# signal_conditioner.net
KiCad netlist of a schematic drawn in EAGLE
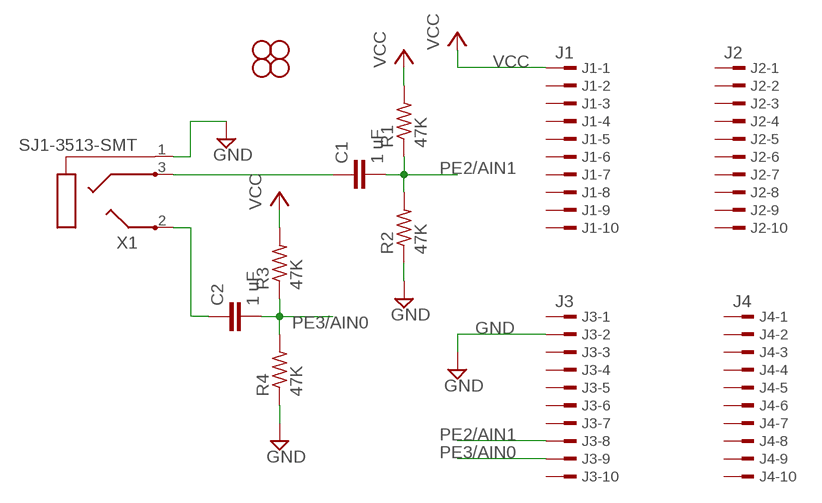
[diagram p0: schematic, sheet 1]

(export (version "E")
  (design (tool "Eeschema 10.0.6"))
  (components
    (comp (ref "C1")
      (value "1 uF")
      (footprint "eagle-import:C050-025X075")
      (libsource (lib "eagle-import") (part "C-EU050-025X075"))
    )
    (comp (ref "C2")
      (value "1 uF")
      (footprint "eagle-import:C050-025X075")
      (libsource (lib "eagle-import") (part "C-EU050-025X075"))
    )
    (comp (ref "J1")
      (value "J1")
      (footprint "eagle-import:TSW-110-02-S-S")
      (fields (field (name "OC_FARNELL") "unknown") (field (name "OC_NEWARK") "unknown"))
      (libsource (lib "eagle-import") (part "TSW-110-02-S-S"))
    )
    (comp (ref "J2")
      (value "J2")
      (footprint "eagle-import:TSW-110-02-S-S")
      (libsource (lib "eagle-import") (part "TSW-110-02-S-S"))
    )
    (comp (ref "J3")
      (value "J3")
      (footprint "eagle-import:TSW-110-02-S-S")
      (fields (field (name "OC_FARNELL") "unknown") (field (name "OC_NEWARK") "unknown"))
      (libsource (lib "eagle-import") (part "TSW-110-02-S-S"))
    )
    (comp (ref "J4")
      (value "J4")
      (footprint "eagle-import:TSW-110-02-S-S")
      (fields (field (name "OC_FARNELL") "unknown") (field (name "OC_NEWARK") "unknown"))
      (libsource (lib "eagle-import") (part "TSW-110-02-S-S"))
    )
    (comp (ref "JP1")
      (value "STAND-OFF")
      (footprint "eagle-import:STAND-OFF")
      (libsource (lib "eagle-import") (part "STAND-OFF"))
    )
    (comp (ref "JP2")
      (value "STAND-OFF")
      (footprint "eagle-import:STAND-OFF")
      (libsource (lib "eagle-import") (part "STAND-OFF"))
    )
    (comp (ref "JP3")
      (value "STAND-OFF")
      (footprint "eagle-import:STAND-OFF")
      (libsource (lib "eagle-import") (part "STAND-OFF"))
    )
    (comp (ref "JP4")
      (value "STAND-OFF")
      (footprint "eagle-import:STAND-OFF")
      (libsource (lib "eagle-import") (part "STAND-OFF"))
    )
    (comp (ref "R1")
      (value "47K")
      (footprint "eagle-import:0207_7")
      (libsource (lib "eagle-import") (part "R-US_0207/7"))
    )
    (comp (ref "R2")
      (value "47K")
      (footprint "eagle-import:0207_7")
      (libsource (lib "eagle-import") (part "R-US_0207/7"))
    )
    (comp (ref "R3")
      (value "47K")
      (footprint "eagle-import:0207_7")
      (libsource (lib "eagle-import") (part "R-US_0207/7"))
    )
    (comp (ref "R4")
      (value "47K")
      (footprint "eagle-import:0207_7")
      (libsource (lib "eagle-import") (part "R-US_0207/7"))
    )
    (comp (ref "X1")
      (value "SJ1-3513-SMT")
      (footprint "eagle-import:3513")
      (libsource (lib "eagle-import") (part "SJ1-3513-SMT"))
    )
  )
  (nets
    (net (code "1") (name "/PE2{slash}AIN1") (class "Default")
      (node (ref "C1") (pin "2") (pinfunction "2_2") (pintype "passive"))
      (node (ref "J3") (pin "8") (pinfunction "1_8") (pintype "passive"))
      (node (ref "R1") (pin "1") (pinfunction "1_1") (pintype "passive"))
      (node (ref "R2") (pin "2") (pinfunction "2_2") (pintype "passive"))
    )
    (net (code "2") (name "/PE3{slash}AIN0") (class "Default")
      (node (ref "C2") (pin "2") (pinfunction "2_2") (pintype "passive"))
      (node (ref "J3") (pin "9") (pinfunction "1_9") (pintype "passive"))
      (node (ref "R3") (pin "1") (pinfunction "1_1") (pintype "passive"))
      (node (ref "R4") (pin "2") (pinfunction "2_2") (pintype "passive"))
    )
    (net (code "3") (name "GND") (class "Default")
      (node (ref "J3") (pin "2") (pinfunction "1_2") (pintype "passive"))
      (node (ref "R2") (pin "1") (pinfunction "1_1") (pintype "passive"))
      (node (ref "R4") (pin "1") (pinfunction "1_1") (pintype "passive"))
      (node (ref "X1") (pin "1") (pinfunction "EARTH_1") (pintype "passive"))
    )
    (net (code "4") (name "Net-(X1-RING)") (class "Default")
      (node (ref "C1") (pin "1") (pinfunction "1_1") (pintype "passive"))
      (node (ref "X1") (pin "3") (pinfunction "RING_3") (pintype "passive"))
    )
    (net (code "5") (name "Net-(X1-TIP)") (class "Default")
      (node (ref "C2") (pin "1") (pinfunction "1_1") (pintype "passive"))
      (node (ref "X1") (pin "2") (pinfunction "TIP_2") (pintype "passive"))
    )
    (net (code "6") (name "VCC") (class "Default")
      (node (ref "J1") (pin "1") (pinfunction "1_1") (pintype "passive"))
      (node (ref "R1") (pin "2") (pinfunction "2_2") (pintype "passive"))
      (node (ref "R3") (pin "2") (pinfunction "2_2") (pintype "passive"))
    )
    (net (code "7") (name "unconnected-(J1B-1-Pad10)") (class "Default")
      (node (ref "J1") (pin "10") (pinfunction "1_10") (pintype "passive"))
    )
    (net (code "8") (name "unconnected-(J1C-1-Pad2)") (class "Default")
      (node (ref "J1") (pin "2") (pinfunction "1_2") (pintype "passive"))
    )
    (net (code "9") (name "unconnected-(J1D-1-Pad3)") (class "Default")
      (node (ref "J1") (pin "3") (pinfunction "1_3") (pintype "passive"))
    )
    (net (code "10") (name "unconnected-(J1E-1-Pad4)") (class "Default")
      (node (ref "J1") (pin "4") (pinfunction "1_4") (pintype "passive"))
    )
    (net (code "11") (name "unconnected-(J1F-1-Pad5)") (class "Default")
      (node (ref "J1") (pin "5") (pinfunction "1_5") (pintype "passive"))
    )
    (net (code "12") (name "unconnected-(J1G-1-Pad6)") (class "Default")
      (node (ref "J1") (pin "6") (pinfunction "1_6") (pintype "passive"))
    )
    (net (code "13") (name "unconnected-(J1H-1-Pad7)") (class "Default")
      (node (ref "J1") (pin "7") (pinfunction "1_7") (pintype "passive"))
    )
    (net (code "14") (name "unconnected-(J1I-1-Pad8)") (class "Default")
      (node (ref "J1") (pin "8") (pinfunction "1_8") (pintype "passive"))
    )
    (net (code "15") (name "unconnected-(J1J-1-Pad9)") (class "Default")
      (node (ref "J1") (pin "9") (pinfunction "1_9") (pintype "passive"))
    )
    (net (code "16") (name "unconnected-(J2-Pad1)") (class "Default")
      (node (ref "J2") (pin "1") (pinfunction "1_1") (pintype "passive"))
    )
    (net (code "17") (name "unconnected-(J2B-1-Pad10)") (class "Default")
      (node (ref "J2") (pin "10") (pinfunction "1_10") (pintype "passive"))
    )
    (net (code "18") (name "unconnected-(J2C-1-Pad2)") (class "Default")
      (node (ref "J2") (pin "2") (pinfunction "1_2") (pintype "passive"))
    )
    (net (code "19") (name "unconnected-(J2D-1-Pad3)") (class "Default")
      (node (ref "J2") (pin "3") (pinfunction "1_3") (pintype "passive"))
    )
    (net (code "20") (name "unconnected-(J2E-1-Pad4)") (class "Default")
      (node (ref "J2") (pin "4") (pinfunction "1_4") (pintype "passive"))
    )
    (net (code "21") (name "unconnected-(J2F-1-Pad5)") (class "Default")
      (node (ref "J2") (pin "5") (pinfunction "1_5") (pintype "passive"))
    )
    (net (code "22") (name "unconnected-(J2G-1-Pad6)") (class "Default")
      (node (ref "J2") (pin "6") (pinfunction "1_6") (pintype "passive"))
    )
    (net (code "23") (name "unconnected-(J2H-1-Pad7)") (class "Default")
      (node (ref "J2") (pin "7") (pinfunction "1_7") (pintype "passive"))
    )
    (net (code "24") (name "unconnected-(J2I-1-Pad8)") (class "Default")
      (node (ref "J2") (pin "8") (pinfunction "1_8") (pintype "passive"))
    )
    (net (code "25") (name "unconnected-(J2J-1-Pad9)") (class "Default")
      (node (ref "J2") (pin "9") (pinfunction "1_9") (pintype "passive"))
    )
    (net (code "26") (name "unconnected-(J3-Pad1)") (class "Default")
      (node (ref "J3") (pin "1") (pinfunction "1_1") (pintype "passive"))
    )
    (net (code "27") (name "unconnected-(J3B-1-Pad10)") (class "Default")
      (node (ref "J3") (pin "10") (pinfunction "1_10") (pintype "passive"))
    )
    (net (code "28") (name "unconnected-(J3D-1-Pad3)") (class "Default")
      (node (ref "J3") (pin "3") (pinfunction "1_3") (pintype "passive"))
    )
    (net (code "29") (name "unconnected-(J3E-1-Pad4)") (class "Default")
      (node (ref "J3") (pin "4") (pinfunction "1_4") (pintype "passive"))
    )
    (net (code "30") (name "unconnected-(J3F-1-Pad5)") (class "Default")
      (node (ref "J3") (pin "5") (pinfunction "1_5") (pintype "passive"))
    )
    (net (code "31") (name "unconnected-(J3G-1-Pad6)") (class "Default")
      (node (ref "J3") (pin "6") (pinfunction "1_6") (pintype "passive"))
    )
    (net (code "32") (name "unconnected-(J3H-1-Pad7)") (class "Default")
      (node (ref "J3") (pin "7") (pinfunction "1_7") (pintype "passive"))
    )
    (net (code "33") (name "unconnected-(J4-Pad1)") (class "Default")
      (node (ref "J4") (pin "1") (pinfunction "1_1") (pintype "passive"))
    )
    (net (code "34") (name "unconnected-(J4B-1-Pad10)") (class "Default")
      (node (ref "J4") (pin "10") (pinfunction "1_10") (pintype "passive"))
    )
    (net (code "35") (name "unconnected-(J4C-1-Pad2)") (class "Default")
      (node (ref "J4") (pin "2") (pinfunction "1_2") (pintype "passive"))
    )
    (net (code "36") (name "unconnected-(J4D-1-Pad3)") (class "Default")
      (node (ref "J4") (pin "3") (pinfunction "1_3") (pintype "passive"))
    )
    (net (code "37") (name "unconnected-(J4E-1-Pad4)") (class "Default")
      (node (ref "J4") (pin "4") (pinfunction "1_4") (pintype "passive"))
    )
    (net (code "38") (name "unconnected-(J4F-1-Pad5)") (class "Default")
      (node (ref "J4") (pin "5") (pinfunction "1_5") (pintype "passive"))
    )
    (net (code "39") (name "unconnected-(J4G-1-Pad6)") (class "Default")
      (node (ref "J4") (pin "6") (pinfunction "1_6") (pintype "passive"))
    )
    (net (code "40") (name "unconnected-(J4H-1-Pad7)") (class "Default")
      (node (ref "J4") (pin "7") (pinfunction "1_7") (pintype "passive"))
    )
    (net (code "41") (name "unconnected-(J4I-1-Pad8)") (class "Default")
      (node (ref "J4") (pin "8") (pinfunction "1_8") (pintype "passive"))
    )
    (net (code "42") (name "unconnected-(J4J-1-Pad9)") (class "Default")
      (node (ref "J4") (pin "9") (pinfunction "1_9") (pintype "passive"))
    )
  )
)
